# OMODRI_GPIO.net
KiCad netlist of a schematic drawn in Altium Designer
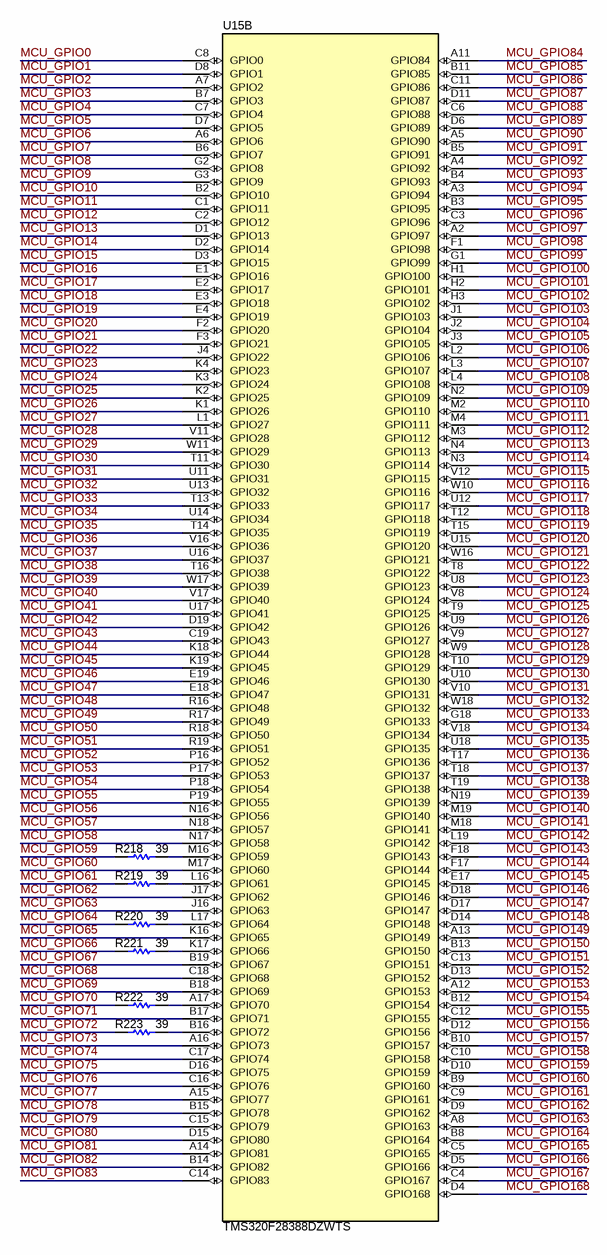
[diagram p0: OMODRI_GPIO.SchDoc]

(export (version "E")
  (design (tool "Eeschema 10.0.6"))
  (components
    (comp (ref "R218")
      (value "CRCW040239R0JNED")
      (footprint "0402")
      (description "RES, 39, 5%, 0.063 W, AEC-Q200 Grade 0, 0402")
      (fields (field (name "MANUFACTURER") "Vishay-Dale") (field (name "VALUEDISPLAYED") "39"))
      (libsource (lib "Altium Vault - TI") (part "Resistor"))
    )
    (comp (ref "R219")
      (value "CRCW040239R0JNED")
      (footprint "0402")
      (description "RES, 39, 5%, 0.063 W, AEC-Q200 Grade 0, 0402")
      (fields (field (name "MANUFACTURER") "Vishay-Dale") (field (name "VALUEDISPLAYED") "39"))
      (libsource (lib "Altium Vault - TI") (part "Resistor"))
    )
    (comp (ref "R220")
      (value "CRCW040239R0JNED")
      (footprint "0402")
      (description "RES, 39, 5%, 0.063 W, AEC-Q200 Grade 0, 0402")
      (fields (field (name "MANUFACTURER") "Vishay-Dale") (field (name "VALUEDISPLAYED") "39"))
      (libsource (lib "Altium Vault - TI") (part "Resistor"))
    )
    (comp (ref "R221")
      (value "CRCW040239R0JNED")
      (footprint "0402")
      (description "RES, 39, 5%, 0.063 W, AEC-Q200 Grade 0, 0402")
      (fields (field (name "MANUFACTURER") "Vishay-Dale") (field (name "VALUEDISPLAYED") "39"))
      (libsource (lib "Altium Vault - TI") (part "Resistor"))
    )
    (comp (ref "R222")
      (value "CRCW040239R0JNED")
      (footprint "0402")
      (description "RES, 39, 5%, 0.063 W, AEC-Q200 Grade 0, 0402")
      (fields (field (name "MANUFACTURER") "Vishay-Dale") (field (name "VALUEDISPLAYED") "39"))
      (libsource (lib "Altium Vault - TI") (part "Resistor"))
    )
    (comp (ref "R223")
      (value "CRCW040239R0JNED")
      (footprint "0402")
      (description "RES, 39, 5%, 0.063 W, AEC-Q200 Grade 0, 0402")
      (fields (field (name "MANUFACTURER") "Vishay-Dale") (field (name "VALUEDISPLAYED") "39"))
      (libsource (lib "Altium Vault - TI") (part "Resistor"))
    )
    (comp (ref "U15")
      (value "TMS320F28388DZWTS")
      (footprint "ZWT0337A")
      (description "TMS320F28388DZWTS, ZWT0337A (NFBGA-337)")
      (fields
        (field (name "PARTNUMBER") "TMS320F28388DZWTS")
        (field (name "MANUFACTURER") "Texas Instruments")
      )
      (libsource (lib "Altium Vault - TI") (part "TMS320F28388"))
    )
  )
  (nets
    (net (code "1") (name "/MCU_GPIO0") (class "Default")
      (node (ref "U15") (pin "C8") (pinfunction "GPIO0_C8") (pintype "bidirectional"))
    )
    (net (code "2") (name "/MCU_GPIO1") (class "Default")
      (node (ref "U15") (pin "D8") (pinfunction "GPIO1_D8") (pintype "bidirectional"))
    )
    (net (code "3") (name "/MCU_GPIO2") (class "Default")
      (node (ref "U15") (pin "A7") (pinfunction "GPIO2_A7") (pintype "bidirectional"))
    )
    (net (code "4") (name "/MCU_GPIO3") (class "Default")
      (node (ref "U15") (pin "B7") (pinfunction "GPIO3_B7") (pintype "bidirectional"))
    )
    (net (code "5") (name "/MCU_GPIO4") (class "Default")
      (node (ref "U15") (pin "C7") (pinfunction "GPIO4_C7") (pintype "bidirectional"))
    )
    (net (code "6") (name "/MCU_GPIO5") (class "Default")
      (node (ref "U15") (pin "D7") (pinfunction "GPIO5_D7") (pintype "bidirectional"))
    )
    (net (code "7") (name "/MCU_GPIO6") (class "Default")
      (node (ref "U15") (pin "A6") (pinfunction "GPIO6_A6") (pintype "bidirectional"))
    )
    (net (code "8") (name "/MCU_GPIO7") (class "Default")
      (node (ref "U15") (pin "B6") (pinfunction "GPIO7_B6") (pintype "bidirectional"))
    )
    (net (code "9") (name "/MCU_GPIO8") (class "Default")
      (node (ref "U15") (pin "G2") (pinfunction "GPIO8_G2") (pintype "bidirectional"))
    )
    (net (code "10") (name "/MCU_GPIO9") (class "Default")
      (node (ref "U15") (pin "G3") (pinfunction "GPIO9_G3") (pintype "bidirectional"))
    )
    (net (code "11") (name "/MCU_GPIO10") (class "Default")
      (node (ref "U15") (pin "B2") (pinfunction "GPIO10_B2") (pintype "bidirectional"))
    )
    (net (code "12") (name "/MCU_GPIO11") (class "Default")
      (node (ref "U15") (pin "C1") (pinfunction "GPIO11_C1") (pintype "bidirectional"))
    )
    (net (code "13") (name "/MCU_GPIO12") (class "Default")
      (node (ref "U15") (pin "C2") (pinfunction "GPIO12_C2") (pintype "bidirectional"))
    )
    (net (code "14") (name "/MCU_GPIO13") (class "Default")
      (node (ref "U15") (pin "D1") (pinfunction "GPIO13_D1") (pintype "bidirectional"))
    )
    (net (code "15") (name "/MCU_GPIO14") (class "Default")
      (node (ref "U15") (pin "D2") (pinfunction "GPIO14_D2") (pintype "bidirectional"))
    )
    (net (code "16") (name "/MCU_GPIO15") (class "Default")
      (node (ref "U15") (pin "D3") (pinfunction "GPIO15_D3") (pintype "bidirectional"))
    )
    (net (code "17") (name "/MCU_GPIO16") (class "Default")
      (node (ref "U15") (pin "E1") (pinfunction "GPIO16_E1") (pintype "bidirectional"))
    )
    (net (code "18") (name "/MCU_GPIO17") (class "Default")
      (node (ref "U15") (pin "E2") (pinfunction "GPIO17_E2") (pintype "bidirectional"))
    )
    (net (code "19") (name "/MCU_GPIO18") (class "Default")
      (node (ref "U15") (pin "E3") (pinfunction "GPIO18_E3") (pintype "bidirectional"))
    )
    (net (code "20") (name "/MCU_GPIO19") (class "Default")
      (node (ref "U15") (pin "E4") (pinfunction "GPIO19_E4") (pintype "bidirectional"))
    )
    (net (code "21") (name "/MCU_GPIO20") (class "Default")
      (node (ref "U15") (pin "F2") (pinfunction "GPIO20_F2") (pintype "bidirectional"))
    )
    (net (code "22") (name "/MCU_GPIO21") (class "Default")
      (node (ref "U15") (pin "F3") (pinfunction "GPIO21_F3") (pintype "bidirectional"))
    )
    (net (code "23") (name "/MCU_GPIO22") (class "Default")
      (node (ref "U15") (pin "J4") (pinfunction "GPIO22_J4") (pintype "bidirectional"))
    )
    (net (code "24") (name "/MCU_GPIO23") (class "Default")
      (node (ref "U15") (pin "K4") (pinfunction "GPIO23_K4") (pintype "bidirectional"))
    )
    (net (code "25") (name "/MCU_GPIO24") (class "Default")
      (node (ref "U15") (pin "K3") (pinfunction "GPIO24_K3") (pintype "bidirectional"))
    )
    (net (code "26") (name "/MCU_GPIO25") (class "Default")
      (node (ref "U15") (pin "K2") (pinfunction "GPIO25_K2") (pintype "bidirectional"))
    )
    (net (code "27") (name "/MCU_GPIO26") (class "Default")
      (node (ref "U15") (pin "K1") (pinfunction "GPIO26_K1") (pintype "bidirectional"))
    )
    (net (code "28") (name "/MCU_GPIO27") (class "Default")
      (node (ref "U15") (pin "L1") (pinfunction "GPIO27_L1") (pintype "bidirectional"))
    )
    (net (code "29") (name "/MCU_GPIO28") (class "Default")
      (node (ref "U15") (pin "V11") (pinfunction "GPIO28_V11") (pintype "bidirectional"))
    )
    (net (code "30") (name "/MCU_GPIO29") (class "Default")
      (node (ref "U15") (pin "W11") (pinfunction "GPIO29_W11") (pintype "bidirectional"))
    )
    (net (code "31") (name "/MCU_GPIO30") (class "Default")
      (node (ref "U15") (pin "T11") (pinfunction "GPIO30_T11") (pintype "bidirectional"))
    )
    (net (code "32") (name "/MCU_GPIO31") (class "Default")
      (node (ref "U15") (pin "U11") (pinfunction "GPIO31_U11") (pintype "bidirectional"))
    )
    (net (code "33") (name "/MCU_GPIO32") (class "Default")
      (node (ref "U15") (pin "U13") (pinfunction "GPIO32_U13") (pintype "bidirectional"))
    )
    (net (code "34") (name "/MCU_GPIO33") (class "Default")
      (node (ref "U15") (pin "T13") (pinfunction "GPIO33_T13") (pintype "bidirectional"))
    )
    (net (code "35") (name "/MCU_GPIO34") (class "Default")
      (node (ref "U15") (pin "U14") (pinfunction "GPIO34_U14") (pintype "bidirectional"))
    )
    (net (code "36") (name "/MCU_GPIO35") (class "Default")
      (node (ref "U15") (pin "T14") (pinfunction "GPIO35_T14") (pintype "bidirectional"))
    )
    (net (code "37") (name "/MCU_GPIO36") (class "Default")
      (node (ref "U15") (pin "V16") (pinfunction "GPIO36_V16") (pintype "bidirectional"))
    )
    (net (code "38") (name "/MCU_GPIO37") (class "Default")
      (node (ref "U15") (pin "U16") (pinfunction "GPIO37_U16") (pintype "bidirectional"))
    )
    (net (code "39") (name "/MCU_GPIO38") (class "Default")
      (node (ref "U15") (pin "T16") (pinfunction "GPIO38_T16") (pintype "bidirectional"))
    )
    (net (code "40") (name "/MCU_GPIO39") (class "Default")
      (node (ref "U15") (pin "W17") (pinfunction "GPIO39_W17") (pintype "bidirectional"))
    )
    (net (code "41") (name "/MCU_GPIO40") (class "Default")
      (node (ref "U15") (pin "V17") (pinfunction "GPIO40_V17") (pintype "bidirectional"))
    )
    (net (code "42") (name "/MCU_GPIO41") (class "Default")
      (node (ref "U15") (pin "U17") (pinfunction "GPIO41_U17") (pintype "bidirectional"))
    )
    (net (code "43") (name "/MCU_GPIO42") (class "Default")
      (node (ref "U15") (pin "D19") (pinfunction "GPIO42_D19") (pintype "bidirectional"))
    )
    (net (code "44") (name "/MCU_GPIO43") (class "Default")
      (node (ref "U15") (pin "C19") (pinfunction "GPIO43_C19") (pintype "bidirectional"))
    )
    (net (code "45") (name "/MCU_GPIO44") (class "Default")
      (node (ref "U15") (pin "K18") (pinfunction "GPIO44_K18") (pintype "bidirectional"))
    )
    (net (code "46") (name "/MCU_GPIO45") (class "Default")
      (node (ref "U15") (pin "K19") (pinfunction "GPIO45_K19") (pintype "bidirectional"))
    )
    (net (code "47") (name "/MCU_GPIO46") (class "Default")
      (node (ref "U15") (pin "E19") (pinfunction "GPIO46_E19") (pintype "bidirectional"))
    )
    (net (code "48") (name "/MCU_GPIO47") (class "Default")
      (node (ref "U15") (pin "E18") (pinfunction "GPIO47_E18") (pintype "bidirectional"))
    )
    (net (code "49") (name "/MCU_GPIO48") (class "Default")
      (node (ref "U15") (pin "R16") (pinfunction "GPIO48_R16") (pintype "bidirectional"))
    )
    (net (code "50") (name "/MCU_GPIO49") (class "Default")
      (node (ref "U15") (pin "R17") (pinfunction "GPIO49_R17") (pintype "bidirectional"))
    )
    (net (code "51") (name "/MCU_GPIO50") (class "Default")
      (node (ref "U15") (pin "R18") (pinfunction "GPIO50_R18") (pintype "bidirectional"))
    )
    (net (code "52") (name "/MCU_GPIO51") (class "Default")
      (node (ref "U15") (pin "R19") (pinfunction "GPIO51_R19") (pintype "bidirectional"))
    )
    (net (code "53") (name "/MCU_GPIO52") (class "Default")
      (node (ref "U15") (pin "P16") (pinfunction "GPIO52_P16") (pintype "bidirectional"))
    )
    (net (code "54") (name "/MCU_GPIO53") (class "Default")
      (node (ref "U15") (pin "P17") (pinfunction "GPIO53_P17") (pintype "bidirectional"))
    )
    (net (code "55") (name "/MCU_GPIO54") (class "Default")
      (node (ref "U15") (pin "P18") (pinfunction "GPIO54_P18") (pintype "bidirectional"))
    )
    (net (code "56") (name "/MCU_GPIO55") (class "Default")
      (node (ref "U15") (pin "P19") (pinfunction "GPIO55_P19") (pintype "bidirectional"))
    )
    (net (code "57") (name "/MCU_GPIO56") (class "Default")
      (node (ref "U15") (pin "N16") (pinfunction "GPIO56_N16") (pintype "bidirectional"))
    )
    (net (code "58") (name "/MCU_GPIO57") (class "Default")
      (node (ref "U15") (pin "N18") (pinfunction "GPIO57_N18") (pintype "bidirectional"))
    )
    (net (code "59") (name "/MCU_GPIO58") (class "Default")
      (node (ref "U15") (pin "N17") (pinfunction "GPIO58_N17") (pintype "bidirectional"))
    )
    (net (code "60") (name "/MCU_GPIO59") (class "Default")
      (node (ref "R218") (pin "1") (pinfunction "1_1") (pintype "passive"))
    )
    (net (code "61") (name "/MCU_GPIO60") (class "Default")
      (node (ref "U15") (pin "M17") (pinfunction "GPIO60_M17") (pintype "bidirectional"))
    )
    (net (code "62") (name "/MCU_GPIO61") (class "Default")
      (node (ref "R219") (pin "1") (pinfunction "1_1") (pintype "passive"))
    )
    (net (code "63") (name "/MCU_GPIO62") (class "Default")
      (node (ref "U15") (pin "J17") (pinfunction "GPIO62_J17") (pintype "bidirectional"))
    )
    (net (code "64") (name "/MCU_GPIO63") (class "Default")
      (node (ref "U15") (pin "J16") (pinfunction "GPIO63_J16") (pintype "bidirectional"))
    )
    (net (code "65") (name "/MCU_GPIO64") (class "Default")
      (node (ref "R220") (pin "1") (pinfunction "1_1") (pintype "passive"))
    )
    (net (code "66") (name "/MCU_GPIO65") (class "Default")
      (node (ref "U15") (pin "K16") (pinfunction "GPIO65_K16") (pintype "bidirectional"))
    )
    (net (code "67") (name "/MCU_GPIO66") (class "Default")
      (node (ref "R221") (pin "1") (pinfunction "1_1") (pintype "passive"))
    )
    (net (code "68") (name "/MCU_GPIO67") (class "Default")
      (node (ref "U15") (pin "B19") (pinfunction "GPIO67_B19") (pintype "bidirectional"))
    )
    (net (code "69") (name "/MCU_GPIO68") (class "Default")
      (node (ref "U15") (pin "C18") (pinfunction "GPIO68_C18") (pintype "bidirectional"))
    )
    (net (code "70") (name "/MCU_GPIO69") (class "Default")
      (node (ref "U15") (pin "B18") (pinfunction "GPIO69_B18") (pintype "bidirectional"))
    )
    (net (code "71") (name "/MCU_GPIO70") (class "Default")
      (node (ref "R222") (pin "1") (pinfunction "1_1") (pintype "passive"))
    )
    (net (code "72") (name "/MCU_GPIO71") (class "Default")
      (node (ref "U15") (pin "B17") (pinfunction "GPIO71_B17") (pintype "bidirectional"))
    )
    (net (code "73") (name "/MCU_GPIO72") (class "Default")
      (node (ref "R223") (pin "1") (pinfunction "1_1") (pintype "passive"))
    )
    (net (code "74") (name "/MCU_GPIO73") (class "Default")
      (node (ref "U15") (pin "A16") (pinfunction "GPIO73_A16") (pintype "bidirectional"))
    )
    (net (code "75") (name "/MCU_GPIO74") (class "Default")
      (node (ref "U15") (pin "C17") (pinfunction "GPIO74_C17") (pintype "bidirectional"))
    )
    (net (code "76") (name "/MCU_GPIO75") (class "Default")
      (node (ref "U15") (pin "D16") (pinfunction "GPIO75_D16") (pintype "bidirectional"))
    )
    (net (code "77") (name "/MCU_GPIO76") (class "Default")
      (node (ref "U15") (pin "C16") (pinfunction "GPIO76_C16") (pintype "bidirectional"))
    )
    (net (code "78") (name "/MCU_GPIO77") (class "Default")
      (node (ref "U15") (pin "A15") (pinfunction "GPIO77_A15") (pintype "bidirectional"))
    )
    (net (code "79") (name "/MCU_GPIO78") (class "Default")
      (node (ref "U15") (pin "B15") (pinfunction "GPIO78_B15") (pintype "bidirectional"))
    )
    (net (code "80") (name "/MCU_GPIO79") (class "Default")
      (node (ref "U15") (pin "C15") (pinfunction "GPIO79_C15") (pintype "bidirectional"))
    )
    (net (code "81") (name "/MCU_GPIO80") (class "Default")
      (node (ref "U15") (pin "D15") (pinfunction "GPIO80_D15") (pintype "bidirectional"))
    )
    (net (code "82") (name "/MCU_GPIO81") (class "Default")
      (node (ref "U15") (pin "A14") (pinfunction "GPIO81_A14") (pintype "bidirectional"))
    )
    (net (code "83") (name "/MCU_GPIO82") (class "Default")
      (node (ref "U15") (pin "B14") (pinfunction "GPIO82_B14") (pintype "bidirectional"))
    )
    (net (code "84") (name "/MCU_GPIO83") (class "Default")
      (node (ref "U15") (pin "C14") (pinfunction "GPIO83_C14") (pintype "bidirectional"))
    )
    (net (code "85") (name "/MCU_GPIO84") (class "Default")
      (node (ref "U15") (pin "A11") (pinfunction "GPIO84_A11") (pintype "bidirectional"))
    )
    (net (code "86") (name "/MCU_GPIO85") (class "Default")
      (node (ref "U15") (pin "B11") (pinfunction "GPIO85_B11") (pintype "bidirectional"))
    )
    (net (code "87") (name "/MCU_GPIO86") (class "Default")
      (node (ref "U15") (pin "C11") (pinfunction "GPIO86_C11") (pintype "bidirectional"))
    )
    (net (code "88") (name "/MCU_GPIO87") (class "Default")
      (node (ref "U15") (pin "D11") (pinfunction "GPIO87_D11") (pintype "bidirectional"))
    )
    (net (code "89") (name "/MCU_GPIO88") (class "Default")
      (node (ref "U15") (pin "C6") (pinfunction "GPIO88_C6") (pintype "bidirectional"))
    )
    (net (code "90") (name "/MCU_GPIO89") (class "Default")
      (node (ref "U15") (pin "D6") (pinfunction "GPIO89_D6") (pintype "bidirectional"))
    )
    (net (code "91") (name "/MCU_GPIO90") (class "Default")
      (node (ref "U15") (pin "A5") (pinfunction "GPIO90_A5") (pintype "bidirectional"))
    )
    (net (code "92") (name "/MCU_GPIO91") (class "Default")
      (node (ref "U15") (pin "B5") (pinfunction "GPIO91_B5") (pintype "bidirectional"))
    )
    (net (code "93") (name "/MCU_GPIO92") (class "Default")
      (node (ref "U15") (pin "A4") (pinfunction "GPIO92_A4") (pintype "bidirectional"))
    )
    (net (code "94") (name "/MCU_GPIO93") (class "Default")
      (node (ref "U15") (pin "B4") (pinfunction "GPIO93_B4") (pintype "bidirectional"))
    )
    (net (code "95") (name "/MCU_GPIO94") (class "Default")
      (node (ref "U15") (pin "A3") (pinfunction "GPIO94_A3") (pintype "bidirectional"))
    )
    (net (code "96") (name "/MCU_GPIO95") (class "Default")
      (node (ref "U15") (pin "B3") (pinfunction "GPIO95_B3") (pintype "bidirectional"))
    )
    (net (code "97") (name "/MCU_GPIO96") (class "Default")
      (node (ref "U15") (pin "C3") (pinfunction "GPIO96_C3") (pintype "bidirectional"))
    )
    (net (code "98") (name "/MCU_GPIO97") (class "Default")
      (node (ref "U15") (pin "A2") (pinfunction "GPIO97_A2") (pintype "bidirectional"))
    )
    (net (code "99") (name "/MCU_GPIO98") (class "Default")
      (node (ref "U15") (pin "F1") (pinfunction "GPIO98_F1") (pintype "bidirectional"))
    )
    (net (code "100") (name "/MCU_GPIO99") (class "Default")
      (node (ref "U15") (pin "G1") (pinfunction "GPIO99_G1") (pintype "bidirectional"))
    )
    (net (code "101") (name "/MCU_GPIO100") (class "Default")
      (node (ref "U15") (pin "H1") (pinfunction "GPIO100_H1") (pintype "bidirectional"))
    )
    (net (code "102") (name "/MCU_GPIO101") (class "Default")
      (node (ref "U15") (pin "H2") (pinfunction "GPIO101_H2") (pintype "bidirectional"))
    )
    (net (code "103") (name "/MCU_GPIO102") (class "Default")
      (node (ref "U15") (pin "H3") (pinfunction "GPIO102_H3") (pintype "bidirectional"))
    )
    (net (code "104") (name "/MCU_GPIO103") (class "Default")
      (node (ref "U15") (pin "J1") (pinfunction "GPIO103_J1") (pintype "bidirectional"))
    )
    (net (code "105") (name "/MCU_GPIO104") (class "Default")
      (node (ref "U15") (pin "J2") (pinfunction "GPIO104_J2") (pintype "bidirectional"))
    )
    (net (code "106") (name "/MCU_GPIO105") (class "Default")
      (node (ref "U15") (pin "J3") (pinfunction "GPIO105_J3") (pintype "bidirectional"))
    )
    (net (code "107") (name "/MCU_GPIO106") (class "Default")
      (node (ref "U15") (pin "L2") (pinfunction "GPIO106_L2") (pintype "bidirectional"))
    )
    (net (code "108") (name "/MCU_GPIO107") (class "Default")
      (node (ref "U15") (pin "L3") (pinfunction "GPIO107_L3") (pintype "bidirectional"))
    )
    (net (code "109") (name "/MCU_GPIO108") (class "Default")
      (node (ref "U15") (pin "L4") (pinfunction "GPIO108_L4") (pintype "bidirectional"))
    )
    (net (code "110") (name "/MCU_GPIO109") (class "Default")
      (node (ref "U15") (pin "N2") (pinfunction "GPIO109_N2") (pintype "bidirectional"))
    )
    (net (code "111") (name "/MCU_GPIO110") (class "Default")
      (node (ref "U15") (pin "M2") (pinfunction "GPIO110_M2") (pintype "bidirectional"))
    )
    (net (code "112") (name "/MCU_GPIO111") (class "Default")
      (node (ref "U15") (pin "M4") (pinfunction "GPIO111_M4") (pintype "bidirectional"))
    )
    (net (code "113") (name "/MCU_GPIO112") (class "Default")
      (node (ref "U15") (pin "M3") (pinfunction "GPIO112_M3") (pintype "bidirectional"))
    )
    (net (code "114") (name "/MCU_GPIO113") (class "Default")
      (node (ref "U15") (pin "N4") (pinfunction "GPIO113_N4") (pintype "bidirectional"))
    )
    (net (code "115") (name "/MCU_GPIO114") (class "Default")
      (node (ref "U15") (pin "N3") (pinfunction "GPIO114_N3") (pintype "bidirectional"))
    )
    (net (code "116") (name "/MCU_GPIO115") (class "Default")
      (node (ref "U15") (pin "V12") (pinfunction "GPIO115_V12") (pintype "bidirectional"))
    )
    (net (code "117") (name "/MCU_GPIO116") (class "Default")
      (node (ref "U15") (pin "W10") (pinfunction "GPIO116_W10") (pintype "bidirectional"))
    )
    (net (code "118") (name "/MCU_GPIO117") (class "Default")
      (node (ref "U15") (pin "U12") (pinfunction "GPIO117_U12") (pintype "bidirectional"))
    )
    (net (code "119") (name "/MCU_GPIO118") (class "Default")
      (node (ref "U15") (pin "T12") (pinfunction "GPIO118_T12") (pintype "bidirectional"))
    )
    (net (code "120") (name "/MCU_GPIO119") (class "Default")
      (node (ref "U15") (pin "T15") (pinfunction "GPIO119_T15") (pintype "bidirectional"))
    )
    (net (code "121") (name "/MCU_GPIO120") (class "Default")
      (node (ref "U15") (pin "U15") (pinfunction "GPIO120_U15") (pintype "bidirectional"))
    )
    (net (code "122") (name "/MCU_GPIO121") (class "Default")
      (node (ref "U15") (pin "W16") (pinfunction "GPIO121_W16") (pintype "bidirectional"))
    )
    (net (code "123") (name "/MCU_GPIO122") (class "Default")
      (node (ref "U15") (pin "T8") (pinfunction "GPIO122_T8") (pintype "bidirectional"))
    )
    (net (code "124") (name "/MCU_GPIO123") (class "Default")
      (node (ref "U15") (pin "U8") (pinfunction "GPIO123_U8") (pintype "bidirectional"))
    )
    (net (code "125") (name "/MCU_GPIO124") (class "Default")
      (node (ref "U15") (pin "V8") (pinfunction "GPIO124_V8") (pintype "bidirectional"))
    )
    (net (code "126") (name "/MCU_GPIO125") (class "Default")
      (node (ref "U15") (pin "T9") (pinfunction "GPIO125_T9") (pintype "bidirectional"))
    )
    (net (code "127") (name "/MCU_GPIO126") (class "Default")
      (node (ref "U15") (pin "U9") (pinfunction "GPIO126_U9") (pintype "bidirectional"))
    )
    (net (code "128") (name "/MCU_GPIO127") (class "Default")
      (node (ref "U15") (pin "V9") (pinfunction "GPIO127_V9") (pintype "bidirectional"))
    )
    (net (code "129") (name "/MCU_GPIO128") (class "Default")
      (node (ref "U15") (pin "W9") (pinfunction "GPIO128_W9") (pintype "bidirectional"))
    )
    (net (code "130") (name "/MCU_GPIO129") (class "Default")
      (node (ref "U15") (pin "T10") (pinfunction "GPIO129_T10") (pintype "bidirectional"))
    )
    (net (code "131") (name "/MCU_GPIO130") (class "Default")
      (node (ref "U15") (pin "U10") (pinfunction "GPIO130_U10") (pintype "bidirectional"))
    )
    (net (code "132") (name "/MCU_GPIO131") (class "Default")
      (node (ref "U15") (pin "V10") (pinfunction "GPIO131_V10") (pintype "bidirectional"))
    )
    (net (code "133") (name "/MCU_GPIO132") (class "Default")
      (node (ref "U15") (pin "W18") (pinfunction "GPIO132_W18") (pintype "bidirectional"))
    )
    (net (code "134") (name "/MCU_GPIO133") (class "Default")
      (node (ref "U15") (pin "G18") (pinfunction "GPIO133_G18") (pintype "bidirectional"))
    )
    (net (code "135") (name "/MCU_GPIO134") (class "Default")
      (node (ref "U15") (pin "V18") (pinfunction "GPIO134_V18") (pintype "bidirectional"))
    )
    (net (code "136") (name "/MCU_GPIO135") (class "Default")
      (node (ref "U15") (pin "U18") (pinfunction "GPIO135_U18") (pintype "bidirectional"))
    )
    (net (code "137") (name "/MCU_GPIO136") (class "Default")
      (node (ref "U15") (pin "T17") (pinfunction "GPIO136_T17") (pintype "bidirectional"))
    )
    (net (code "138") (name "/MCU_GPIO137") (class "Default")
      (node (ref "U15") (pin "T18") (pinfunction "GPIO137_T18") (pintype "bidirectional"))
    )
    (net (code "139") (name "/MCU_GPIO138") (class "Default")
      (node (ref "U15") (pin "T19") (pinfunction "GPIO138_T19") (pintype "bidirectional"))
    )
    (net (code "140") (name "/MCU_GPIO139") (class "Default")
      (node (ref "U15") (pin "N19") (pinfunction "GPIO139_N19") (pintype "bidirectional"))
    )
    (net (code "141") (name "/MCU_GPIO140") (class "Default")
      (node (ref "U15") (pin "M19") (pinfunction "GPIO140_M19") (pintype "bidirectional"))
    )
    (net (code "142") (name "/MCU_GPIO141") (class "Default")
      (node (ref "U15") (pin "M18") (pinfunction "GPIO141_M18") (pintype "bidirectional"))
    )
    (net (code "143") (name "/MCU_GPIO142") (class "Default")
      (node (ref "U15") (pin "L19") (pinfunction "GPIO142_L19") (pintype "bidirectional"))
    )
    (net (code "144") (name "/MCU_GPIO143") (class "Default")
      (node (ref "U15") (pin "F18") (pinfunction "GPIO143_F18") (pintype "bidirectional"))
    )
    (net (code "145") (name "/MCU_GPIO144") (class "Default")
      (node (ref "U15") (pin "F17") (pinfunction "GPIO144_F17") (pintype "bidirectional"))
    )
    (net (code "146") (name "/MCU_GPIO145") (class "Default")
      (node (ref "U15") (pin "E17") (pinfunction "GPIO145_E17") (pintype "bidirectional"))
    )
    (net (code "147") (name "/MCU_GPIO146") (class "Default")
      (node (ref "U15") (pin "D18") (pinfunction "GPIO146_D18") (pintype "bidirectional"))
    )
    (net (code "148") (name "/MCU_GPIO147") (class "Default")
      (node (ref "U15") (pin "D17") (pinfunction "GPIO147_D17") (pintype "bidirectional"))
    )
    (net (code "149") (name "/MCU_GPIO148") (class "Default")
      (node (ref "U15") (pin "D14") (pinfunction "GPIO148_D14") (pintype "bidirectional"))
    )
    (net (code "150") (name "/MCU_GPIO149") (class "Default")
      (node (ref "U15") (pin "A13") (pinfunction "GPIO149_A13") (pintype "bidirectional"))
    )
    (net (code "151") (name "/MCU_GPIO150") (class "Default")
      (node (ref "U15") (pin "B13") (pinfunction "GPIO150_B13") (pintype "bidirectional"))
    )
    (net (code "152") (name "/MCU_GPIO151") (class "Default")
      (node (ref "U15") (pin "C13") (pinfunction "GPIO151_C13") (pintype "bidirectional"))
    )
    (net (code "153") (name "/MCU_GPIO152") (class "Default")
      (node (ref "U15") (pin "D13") (pinfunction "GPIO152_D13") (pintype "bidirectional"))
    )
    (net (code "154") (name "/MCU_GPIO153") (class "Default")
      (node (ref "U15") (pin "A12") (pinfunction "GPIO153_A12") (pintype "bidirectional"))
    )
    (net (code "155") (name "/MCU_GPIO154") (class "Default")
      (node (ref "U15") (pin "B12") (pinfunction "GPIO154_B12") (pintype "bidirectional"))
    )
    (net (code "156") (name "/MCU_GPIO155") (class "Default")
      (node (ref "U15") (pin "C12") (pinfunction "GPIO155_C12") (pintype "bidirectional"))
    )
    (net (code "157") (name "/MCU_GPIO156") (class "Default")
      (node (ref "U15") (pin "D12") (pinfunction "GPIO156_D12") (pintype "bidirectional"))
    )
    (net (code "158") (name "/MCU_GPIO157") (class "Default")
      (node (ref "U15") (pin "B10") (pinfunction "GPIO157_B10") (pintype "bidirectional"))
    )
    (net (code "159") (name "/MCU_GPIO158") (class "Default")
      (node (ref "U15") (pin "C10") (pinfunction "GPIO158_C10") (pintype "bidirectional"))
    )
    (net (code "160") (name "/MCU_GPIO159") (class "Default")
      (node (ref "U15") (pin "D10") (pinfunction "GPIO159_D10") (pintype "bidirectional"))
    )
    (net (code "161") (name "/MCU_GPIO160") (class "Default")
      (node (ref "U15") (pin "B9") (pinfunction "GPIO160_B9") (pintype "bidirectional"))
    )
    (net (code "162") (name "/MCU_GPIO161") (class "Default")
      (node (ref "U15") (pin "C9") (pinfunction "GPIO161_C9") (pintype "bidirectional"))
    )
    (net (code "163") (name "/MCU_GPIO162") (class "Default")
      (node (ref "U15") (pin "D9") (pinfunction "GPIO162_D9") (pintype "bidirectional"))
    )
    (net (code "164") (name "/MCU_GPIO163") (class "Default")
      (node (ref "U15") (pin "A8") (pinfunction "GPIO163_A8") (pintype "bidirectional"))
    )
    (net (code "165") (name "/MCU_GPIO164") (class "Default")
      (node (ref "U15") (pin "B8") (pinfunction "GPIO164_B8") (pintype "bidirectional"))
    )
    (net (code "166") (name "/MCU_GPIO165") (class "Default")
      (node (ref "U15") (pin "C5") (pinfunction "GPIO165_C5") (pintype "bidirectional"))
    )
    (net (code "167") (name "/MCU_GPIO166") (class "Default")
      (node (ref "U15") (pin "D5") (pinfunction "GPIO166_D5") (pintype "bidirectional"))
    )
    (net (code "168") (name "/MCU_GPIO167") (class "Default")
      (node (ref "U15") (pin "C4") (pinfunction "GPIO167_C4") (pintype "bidirectional"))
    )
    (net (code "169") (name "/MCU_GPIO168") (class "Default")
      (node (ref "U15") (pin "D4") (pinfunction "GPIO168_D4") (pintype "bidirectional"))
    )
    (net (code "170") (name "Net-(U15B-GPIO59)") (class "Default")
      (node (ref "R218") (pin "2") (pinfunction "2_2") (pintype "passive"))
      (node (ref "U15") (pin "M16") (pinfunction "GPIO59_M16") (pintype "bidirectional"))
    )
    (net (code "171") (name "Net-(U15B-GPIO61)") (class "Default")
      (node (ref "R219") (pin "2") (pinfunction "2_2") (pintype "passive"))
      (node (ref "U15") (pin "L16") (pinfunction "GPIO61_L16") (pintype "bidirectional"))
    )
    (net (code "172") (name "Net-(U15B-GPIO64)") (class "Default")
      (node (ref "R220") (pin "2") (pinfunction "2_2") (pintype "passive"))
      (node (ref "U15") (pin "L17") (pinfunction "GPIO64_L17") (pintype "bidirectional"))
    )
    (net (code "173") (name "Net-(U15B-GPIO66)") (class "Default")
      (node (ref "R221") (pin "2") (pinfunction "2_2") (pintype "passive"))
      (node (ref "U15") (pin "K17") (pinfunction "GPIO66_K17") (pintype "bidirectional"))
    )
    (net (code "174") (name "Net-(U15B-GPIO70)") (class "Default")
      (node (ref "R222") (pin "2") (pinfunction "2_2") (pintype "passive"))
      (node (ref "U15") (pin "A17") (pinfunction "GPIO70_A17") (pintype "bidirectional"))
    )
    (net (code "175") (name "Net-(U15B-GPIO72)") (class "Default")
      (node (ref "R223") (pin "2") (pinfunction "2_2") (pintype "passive"))
      (node (ref "U15") (pin "B16") (pinfunction "GPIO72_B16") (pintype "bidirectional"))
    )
  )
)
